# parallelNGtest.net
KiCad netlist of a schematic drawn in EAGLE
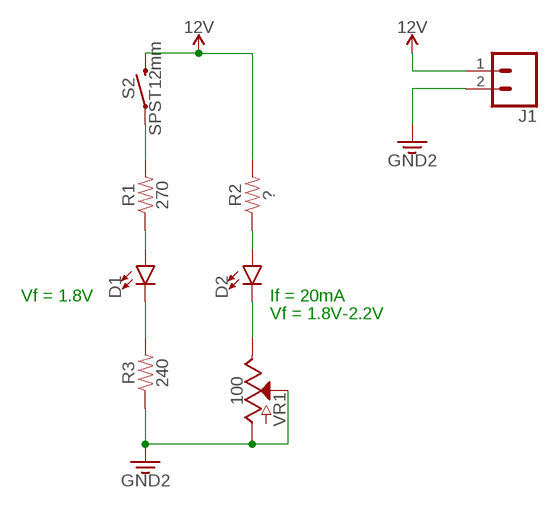
[diagram p0: schematic, sheet 1]

(export (version "E")
  (design (tool "Eeschema 10.0.6"))
  (components
    (comp (ref "D1")
      (value "LED5MM")
      (footprint "eagle-import:LED_5MM")
      (libsource (lib "eagle-import") (part "LED5MM"))
    )
    (comp (ref "D2")
      (value "LED5MM")
      (footprint "eagle-import:LED_5MM")
      (libsource (lib "eagle-import") (part "LED5MM"))
    )
    (comp (ref "J1")
      (value "CONN_02PTH4")
      (footprint "eagle-import:1X02_XTRA_BIG")
      (libsource (lib "eagle-import") (part "CONN_02PTH4"))
    )
    (comp (ref "R1")
      (value "270")
      (footprint "eagle-import:AXIAL-0.3")
      (libsource (lib "eagle-import") (part "RESISTORAXIAL-0.3"))
    )
    (comp (ref "R2")
      (value "?")
      (footprint "eagle-import:AXIAL-0.3")
      (libsource (lib "eagle-import") (part "RESISTORAXIAL-0.3"))
    )
    (comp (ref "R3")
      (value "240")
      (footprint "eagle-import:AXIAL-0.3")
      (libsource (lib "eagle-import") (part "RESISTORAXIAL-0.3"))
    )
    (comp (ref "S2")
      (value "SPST12mm")
      (footprint "eagle-import:TACTILE_SWITCH_PTH_12MM")
      (libsource (lib "eagle-import") (part "MOMENTARY-SWITCH-SPST-PTH-12MM"))
    )
    (comp (ref "VR1")
      (value "100")
      (footprint "eagle-import:POT-PTH-ALPS")
      (libsource (lib "eagle-import") (part "POTENTIOMETER-PTH-9MM-1/20W-20%"))
    )
  )
  (nets
    (net (code "1") (name "12V") (class "Default")
      (node (ref "J1") (pin "1") (pinfunction "1_1") (pintype "passive"))
      (node (ref "R2") (pin "P$2") (pinfunction "2_P$2") (pintype "passive"))
      (node (ref "S2") (pin "3") (pinfunction "2_3") (pintype "passive"))
    )
    (net (code "2") (name "GND2") (class "Default")
      (node (ref "J1") (pin "2") (pinfunction "2_2") (pintype "passive"))
      (node (ref "R3") (pin "P$1") (pinfunction "1_P$1") (pintype "passive"))
      (node (ref "VR1") (pin "P$2") (pinfunction "S_P$2") (pintype "passive"))
      (node (ref "VR1") (pin "P$3") (pinfunction "A_P$3") (pintype "passive"))
    )
    (net (code "3") (name "Net-(D1-C)") (class "Default")
      (node (ref "D1") (pin "K") (pinfunction "C_K") (pintype "passive"))
      (node (ref "R3") (pin "P$2") (pinfunction "2_P$2") (pintype "passive"))
    )
    (net (code "4") (name "Net-(D2-C)") (class "Default")
      (node (ref "D2") (pin "K") (pinfunction "C_K") (pintype "passive"))
      (node (ref "VR1") (pin "P$1") (pinfunction "E_P$1") (pintype "passive"))
    )
    (net (code "5") (name "Net-(R1-1)") (class "Default")
      (node (ref "D1") (pin "A") (pinfunction "A_A") (pintype "passive"))
      (node (ref "R1") (pin "P$1") (pinfunction "1_P$1") (pintype "passive"))
    )
    (net (code "6") (name "Net-(R1-2)") (class "Default")
      (node (ref "R1") (pin "P$2") (pinfunction "2_P$2") (pintype "passive"))
      (node (ref "S2") (pin "1") (pinfunction "1_1") (pintype "passive"))
    )
    (net (code "7") (name "Net-(R2-1)") (class "Default")
      (node (ref "D2") (pin "A") (pinfunction "A_A") (pintype "passive"))
      (node (ref "R2") (pin "P$1") (pinfunction "1_P$1") (pintype "passive"))
    )
  )
)
